# Input_and_Safety.net
KiCad netlist of a schematic drawn in Altium Designer
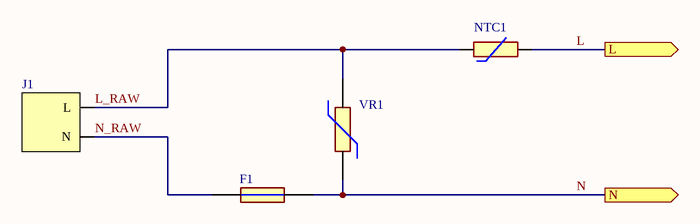
[diagram p0: Input and Safety.SchDoc]

(export (version "E")
  (design (tool "Eeschema 10.0.6"))
  (components
    (comp (ref "F1")
      (value "250V 2.5A")
      (footprint "C310T-SC-2-5-R-TR1")
      (description "Cartridge Fuses 2.5A 250V high I2t ceramic")
      (libsource (lib "SMPS Schlib") (part "C310T-SC-2-5-R-TR1"))
    )
    (comp (ref "J1")
      (value "250VAC")
      (footprint "691102710002")
      (description "Fixed Terminal Blocks WR-TBL 300VAC 15A 2P Straight")
      (libsource (lib "SMPS Schlib") (part "691102710002"))
    )
    (comp (ref "NTC1")
      (value "230V 2A")
      (footprint "B57153S0100M051")
      (description "Inrush Current Limiters S 153/10 M51")
      (libsource (lib "SMPS Schlib") (part "B57153S0100M051"))
    )
    (comp (ref "VR1")
      (value "275VAC")
      (footprint "B72307S0271K101")
      (description "Varistors 7mm, 275Vac, 10%, Compact Series")
      (libsource (lib "SMPS Schlib") (part "B72307S0271K101"))
    )
  )
  (nets
    (net (code "1") (name "/L") (class "Default")
      (node (ref "NTC1") (pin "2") (pinfunction "2_2") (pintype "passive"))
    )
    (net (code "2") (name "/L_RAW") (class "Default")
      (node (ref "J1") (pin "1") (pinfunction "L_1") (pintype "passive"))
      (node (ref "NTC1") (pin "1") (pinfunction "1_1") (pintype "passive"))
      (node (ref "VR1") (pin "2") (pinfunction "2_2") (pintype "passive"))
    )
    (net (code "3") (name "/N") (class "Default")
      (node (ref "F1") (pin "2") (pinfunction "2_2") (pintype "passive"))
      (node (ref "VR1") (pin "1") (pinfunction "1_1") (pintype "passive"))
    )
    (net (code "4") (name "/N_RAW") (class "Default")
      (node (ref "F1") (pin "1") (pinfunction "1_1") (pintype "passive"))
      (node (ref "J1") (pin "2") (pinfunction "N_2") (pintype "passive"))
    )
  )
)
